# modul_aid.net
KiCad netlist of a schematic drawn in EAGLE
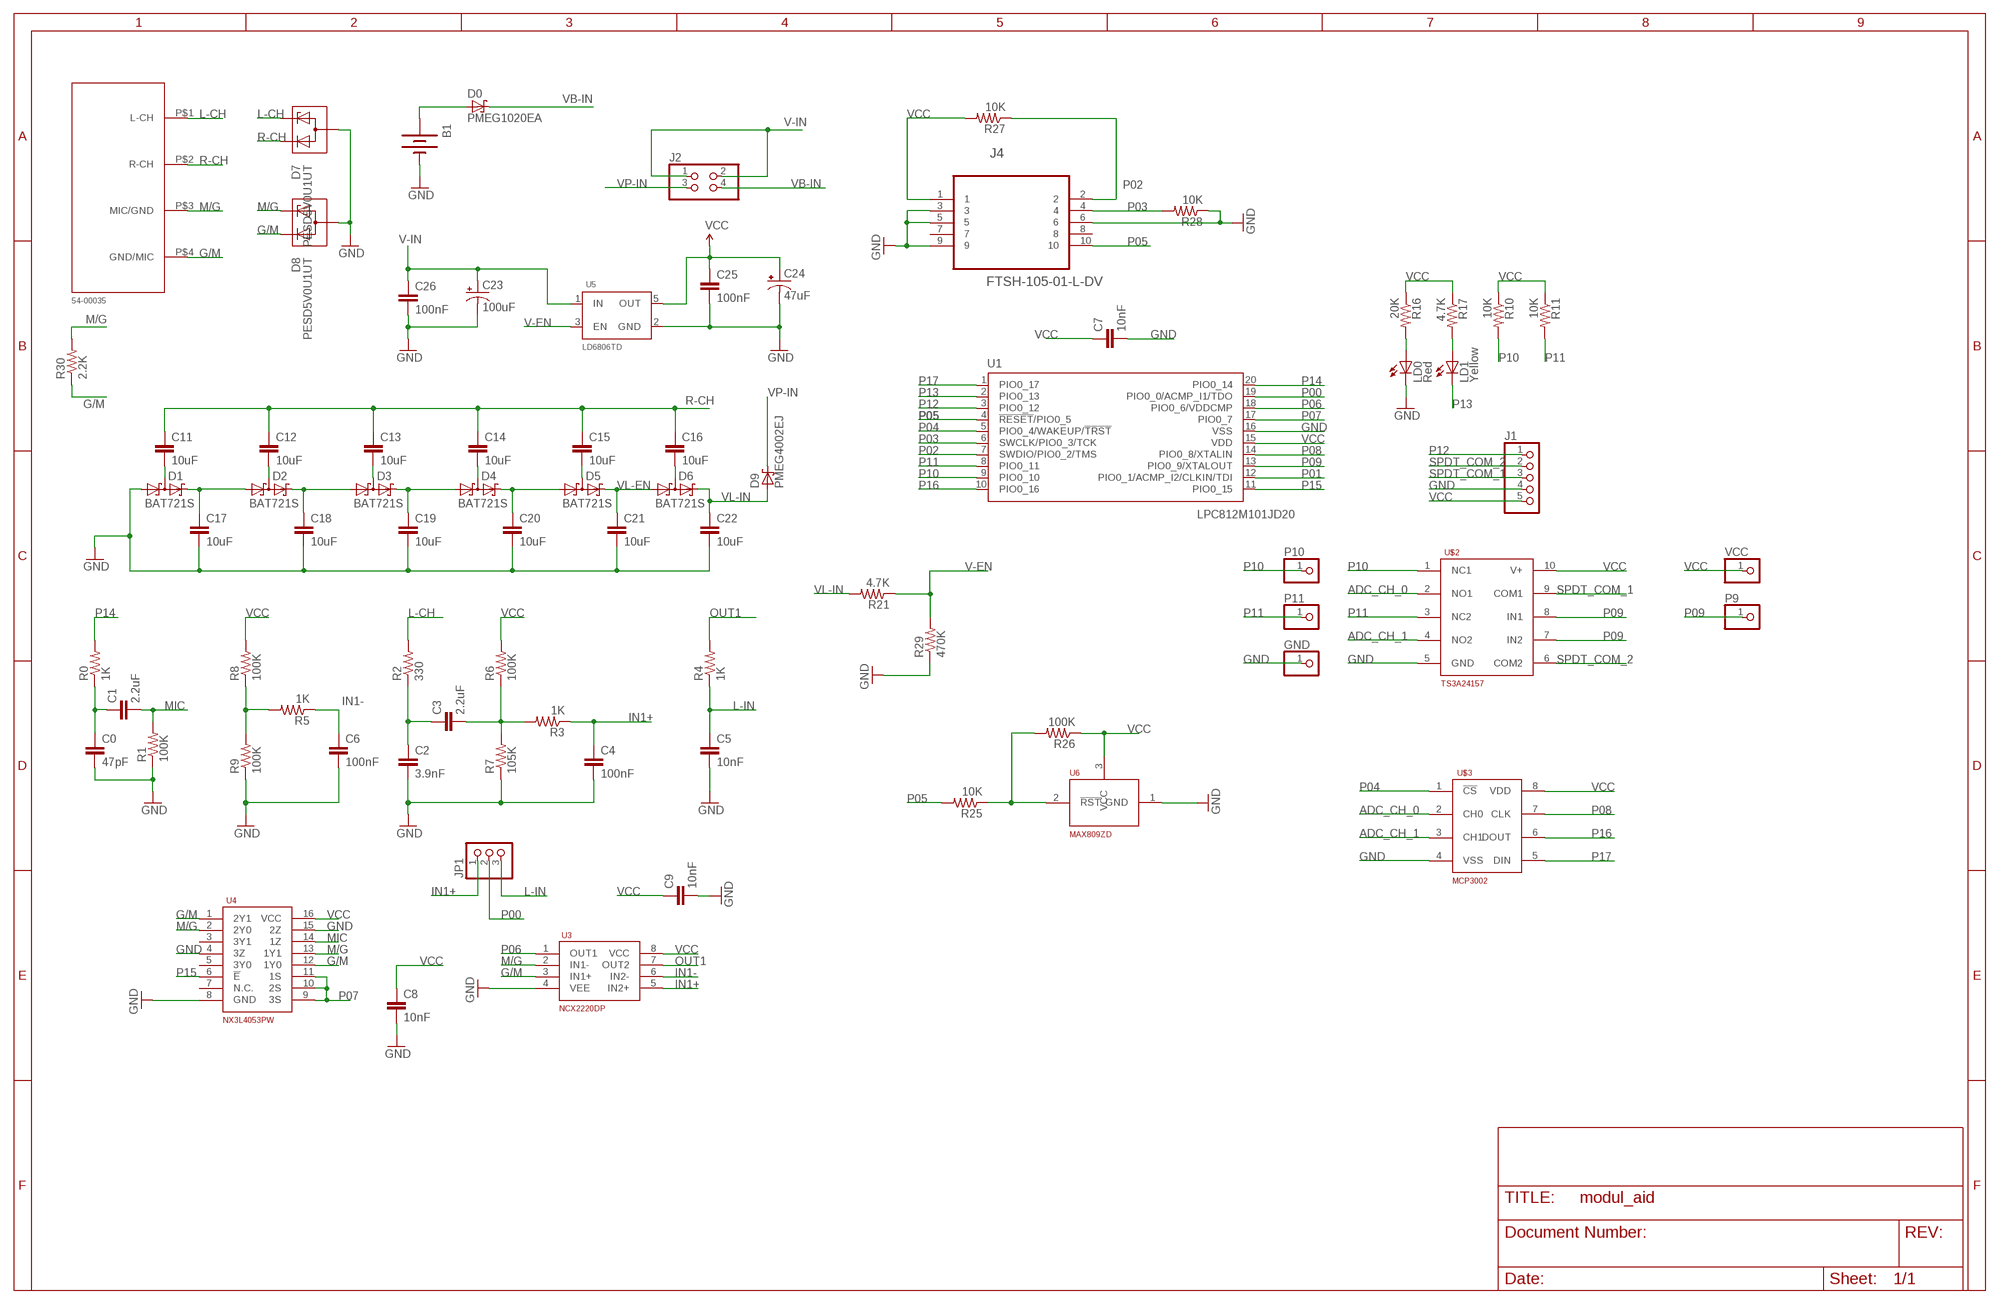
[diagram p0: schematic, sheet 1]

(export (version "E")
  (design (tool "Eeschema 10.0.6"))
  (components
    (comp (ref "B1")
      (value "BATTERY20PTH")
      (footprint "eagle-import:BATTCOM_20MM_PTH")
      (libsource (lib "eagle-import") (part "BATTERY20PTH"))
    )
    (comp (ref "C0")
      (value "47pF")
      (footprint "eagle-import:0805-CAP")
      (libsource (lib "eagle-import") (part "10UF10V10%(0805)"))
    )
    (comp (ref "C1")
      (value "2.2uF")
      (footprint "eagle-import:0805-CAP")
      (libsource (lib "eagle-import") (part "10UF10V10%(0805)"))
    )
    (comp (ref "C2")
      (value "3.9nF")
      (footprint "eagle-import:0805-CAP")
      (libsource (lib "eagle-import") (part "10UF10V10%(0805)"))
    )
    (comp (ref "C3")
      (value "2.2uF")
      (footprint "eagle-import:0805-CAP")
      (libsource (lib "eagle-import") (part "10UF10V10%(0805)"))
    )
    (comp (ref "C4")
      (value "100nF")
      (footprint "eagle-import:0805-CAP")
      (libsource (lib "eagle-import") (part "10UF10V10%(0805)"))
    )
    (comp (ref "C5")
      (value "10nF")
      (footprint "eagle-import:0805-CAP")
      (libsource (lib "eagle-import") (part "10UF10V10%(0805)"))
    )
    (comp (ref "C6")
      (value "100nF")
      (footprint "eagle-import:0805-CAP")
      (libsource (lib "eagle-import") (part "10UF10V10%(0805)"))
    )
    (comp (ref "C7")
      (value "10nF")
      (footprint "eagle-import:0805")
      (libsource (lib "eagle-import") (part "CAP0805"))
    )
    (comp (ref "C8")
      (value "10nF")
      (footprint "eagle-import:0805-CAP")
      (libsource (lib "eagle-import") (part "10UF10V10%(0805)"))
    )
    (comp (ref "C9")
      (value "10nF")
      (footprint "eagle-import:0805-CAP")
      (libsource (lib "eagle-import") (part "10UF10V10%(0805)"))
    )
    (comp (ref "C11")
      (value "10uF")
      (footprint "eagle-import:0805-CAP")
      (libsource (lib "eagle-import") (part "10UF10V10%(0805)"))
    )
    (comp (ref "C12")
      (value "10uF")
      (footprint "eagle-import:0805-CAP")
      (libsource (lib "eagle-import") (part "10UF10V10%(0805)"))
    )
    (comp (ref "C13")
      (value "10uF")
      (footprint "eagle-import:0805-CAP")
      (libsource (lib "eagle-import") (part "10UF10V10%(0805)"))
    )
    (comp (ref "C14")
      (value "10uF")
      (footprint "eagle-import:0805-CAP")
      (libsource (lib "eagle-import") (part "10UF10V10%(0805)"))
    )
    (comp (ref "C15")
      (value "10uF")
      (footprint "eagle-import:0805-CAP")
      (libsource (lib "eagle-import") (part "10UF10V10%(0805)"))
    )
    (comp (ref "C16")
      (value "10uF")
      (footprint "eagle-import:0805-CAP")
      (libsource (lib "eagle-import") (part "10UF10V10%(0805)"))
    )
    (comp (ref "C17")
      (value "10uF")
      (footprint "eagle-import:0805-CAP")
      (libsource (lib "eagle-import") (part "10UF10V10%(0805)"))
    )
    (comp (ref "C18")
      (value "10uF")
      (footprint "eagle-import:0805-CAP")
      (libsource (lib "eagle-import") (part "10UF10V10%(0805)"))
    )
    (comp (ref "C19")
      (value "10uF")
      (footprint "eagle-import:0805-CAP")
      (libsource (lib "eagle-import") (part "10UF10V10%(0805)"))
    )
    (comp (ref "C20")
      (value "10uF")
      (footprint "eagle-import:0805-CAP")
      (libsource (lib "eagle-import") (part "10UF10V10%(0805)"))
    )
    (comp (ref "C21")
      (value "10uF")
      (footprint "eagle-import:0805-CAP")
      (libsource (lib "eagle-import") (part "10UF10V10%(0805)"))
    )
    (comp (ref "C22")
      (value "10uF")
      (footprint "eagle-import:0805-CAP")
      (libsource (lib "eagle-import") (part "10UF10V10%(0805)"))
    )
    (comp (ref "C23")
      (value "100uF")
      (footprint "eagle-import:EIA3216-KIT")
      (libsource (lib "eagle-import") (part "CAP_POL1206-KIT"))
    )
    (comp (ref "C24")
      (value "47uF")
      (footprint "eagle-import:EIA3216-KIT")
      (libsource (lib "eagle-import") (part "CAP_POL1206-KIT"))
    )
    (comp (ref "C25")
      (value "100nF")
      (footprint "eagle-import:0805")
      (libsource (lib "eagle-import") (part "CAP0805"))
    )
    (comp (ref "C26")
      (value "100nF")
      (footprint "eagle-import:0805")
      (libsource (lib "eagle-import") (part "CAP0805"))
    )
    (comp (ref "D0")
      (value "PMEG1020EA")
      (footprint "eagle-import:SOD323(F)")
      (libsource (lib "eagle-import") (part "PMEG1020EA"))
    )
    (comp (ref "D1")
      (value "BAT721S")
      (footprint "eagle-import:SOT23")
      (libsource (lib "eagle-import") (part "BAT721S"))
    )
    (comp (ref "D2")
      (value "BAT721S")
      (footprint "eagle-import:SOT23")
      (libsource (lib "eagle-import") (part "BAT721S"))
    )
    (comp (ref "D3")
      (value "BAT721S")
      (footprint "eagle-import:SOT23")
      (libsource (lib "eagle-import") (part "BAT721S"))
    )
    (comp (ref "D4")
      (value "BAT721S")
      (footprint "eagle-import:SOT23")
      (libsource (lib "eagle-import") (part "BAT721S"))
    )
    (comp (ref "D5")
      (value "BAT721S")
      (footprint "eagle-import:SOT23")
      (libsource (lib "eagle-import") (part "BAT721S"))
    )
    (comp (ref "D6")
      (value "BAT721S")
      (footprint "eagle-import:SOT23")
      (libsource (lib "eagle-import") (part "BAT721S"))
    )
    (comp (ref "D7")
      (value "PESD5V0U1UT")
      (footprint "eagle-import:SOT23")
      (libsource (lib "eagle-import") (part "PESD5V0U1UT"))
    )
    (comp (ref "D8")
      (value "PESD5V0U1UT")
      (footprint "eagle-import:SOT23")
      (libsource (lib "eagle-import") (part "PESD5V0U1UT"))
    )
    (comp (ref "D9")
      (value "PMEG4002EJ")
      (footprint "eagle-import:SOD323(F)")
      (libsource (lib "eagle-import") (part "PMEG4002EJ"))
    )
    (comp (ref "GND")
      (value "PINHD-1X1")
      (footprint "eagle-import:1X01")
      (libsource (lib "eagle-import") (part "PINHD-1X1"))
    )
    (comp (ref "J1")
      (value "PINHD-1X5")
      (footprint "eagle-import:1X05")
      (libsource (lib "eagle-import") (part "PINHD-1X5"))
    )
    (comp (ref "J2")
      (value "PINHD-2X2")
      (footprint "eagle-import:2X02")
      (libsource (lib "eagle-import") (part "PINHD-2X2"))
    )
    (comp (ref "J4")
      (value "FTSH-105-01-L-DV")
      (footprint "eagle-import:SAMTEC_FTSH-105-01-L-DV")
      (libsource (lib "eagle-import") (part "FTSH-105-01-L-DV"))
    )
    (comp (ref "JP1")
      (value "PINHD-1X3")
      (footprint "eagle-import:1X03")
      (libsource (lib "eagle-import") (part "PINHD-1X3"))
    )
    (comp (ref "LD0")
      (value "Red")
      (footprint "eagle-import:SML0805")
      (libsource (lib "eagle-import") (part "LEDSML0805"))
    )
    (comp (ref "LD1")
      (value "Yellow")
      (footprint "eagle-import:SML0805")
      (libsource (lib "eagle-import") (part "LEDSML0805"))
    )
    (comp (ref "P9")
      (value "PINHD-1X1")
      (footprint "eagle-import:1X01")
      (libsource (lib "eagle-import") (part "PINHD-1X1"))
    )
    (comp (ref "P10")
      (value "PINHD-1X1")
      (footprint "eagle-import:1X01")
      (libsource (lib "eagle-import") (part "PINHD-1X1"))
    )
    (comp (ref "P11")
      (value "PINHD-1X1")
      (footprint "eagle-import:1X01")
      (libsource (lib "eagle-import") (part "PINHD-1X1"))
    )
    (comp (ref "R0")
      (value "1K")
      (footprint "eagle-import:0805")
      (libsource (lib "eagle-import") (part "RESISTOR0805-RES"))
    )
    (comp (ref "R1")
      (value "100K")
      (footprint "eagle-import:0805")
      (libsource (lib "eagle-import") (part "RESISTOR0805-RES"))
    )
    (comp (ref "R2")
      (value "330")
      (footprint "eagle-import:0805")
      (libsource (lib "eagle-import") (part "RESISTOR0805-RES"))
    )
    (comp (ref "R3")
      (value "1K")
      (footprint "eagle-import:0805")
      (libsource (lib "eagle-import") (part "RESISTOR0805-RES"))
    )
    (comp (ref "R4")
      (value "1K")
      (footprint "eagle-import:0805")
      (libsource (lib "eagle-import") (part "RESISTOR0805-RES"))
    )
    (comp (ref "R5")
      (value "1K")
      (footprint "eagle-import:0805")
      (libsource (lib "eagle-import") (part "RESISTOR0805-RES"))
    )
    (comp (ref "R6")
      (value "100K")
      (footprint "eagle-import:0805")
      (libsource (lib "eagle-import") (part "RESISTOR0805-RES"))
    )
    (comp (ref "R7")
      (value "105K")
      (footprint "eagle-import:0805")
      (libsource (lib "eagle-import") (part "RESISTOR0805-RES"))
    )
    (comp (ref "R8")
      (value "100K")
      (footprint "eagle-import:0805")
      (libsource (lib "eagle-import") (part "RESISTOR0805-RES"))
    )
    (comp (ref "R9")
      (value "100K")
      (footprint "eagle-import:0805")
      (libsource (lib "eagle-import") (part "RESISTOR0805-RES"))
    )
    (comp (ref "R10")
      (value "10K")
      (footprint "eagle-import:0805")
      (libsource (lib "eagle-import") (part "RESISTOR0805-RES"))
    )
    (comp (ref "R11")
      (value "10K")
      (footprint "eagle-import:0805")
      (libsource (lib "eagle-import") (part "RESISTOR0805-RES"))
    )
    (comp (ref "R16")
      (value "20K")
      (footprint "eagle-import:0805")
      (libsource (lib "eagle-import") (part "RESISTOR0805-RES"))
    )
    (comp (ref "R17")
      (value "4.7K")
      (footprint "eagle-import:0805")
      (libsource (lib "eagle-import") (part "RESISTOR0805-RES"))
    )
    (comp (ref "R21")
      (value "4.7K")
      (footprint "eagle-import:0805")
      (libsource (lib "eagle-import") (part "RESISTOR0805-RES"))
    )
    (comp (ref "R25")
      (value "10K")
      (footprint "eagle-import:0805")
      (libsource (lib "eagle-import") (part "RESISTOR0805-RES"))
    )
    (comp (ref "R26")
      (value "100K")
      (footprint "eagle-import:0805")
      (libsource (lib "eagle-import") (part "RESISTOR0805-RES"))
    )
    (comp (ref "R27")
      (value "10K")
      (footprint "eagle-import:0805")
      (libsource (lib "eagle-import") (part "RESISTOR0805-RES"))
    )
    (comp (ref "R28")
      (value "10K")
      (footprint "eagle-import:0805")
      (libsource (lib "eagle-import") (part "RESISTOR0805-RES"))
    )
    (comp (ref "R29")
      (value "470K")
      (footprint "eagle-import:0805")
      (libsource (lib "eagle-import") (part "RESISTOR0805-RES"))
    )
    (comp (ref "R30")
      (value "2.2K")
      (footprint "eagle-import:0805")
      (libsource (lib "eagle-import") (part "RESISTOR0805-RES"))
    )
    (comp (ref "U$2")
      (value "TS3A24157")
      (footprint "eagle-import:VSSOP-10")
      (libsource (lib "eagle-import") (part "TS3A24157"))
    )
    (comp (ref "U$3")
      (value "MCP3002")
      (footprint "eagle-import:SOIC8")
      (libsource (lib "eagle-import") (part "MCP3002"))
    )
    (comp (ref "U$4")
      (value "TENSILITY54-00035")
      (footprint "eagle-import:EE464SAUDIOJACK")
      (libsource (lib "eagle-import") (part "TENSILITY54-00035"))
    )
    (comp (ref "U1")
      (value "LPC812M101JD20")
      (footprint "eagle-import:SOT163-1")
      (libsource (lib "eagle-import") (part "LPC812M101JD20"))
    )
    (comp (ref "U3")
      (value "NCX2220DP")
      (footprint "eagle-import:SOT505-2")
      (libsource (lib "eagle-import") (part "NCX2220DP"))
    )
    (comp (ref "U4")
      (value "NX3L4053PW")
      (footprint "eagle-import:S0T403-1")
      (libsource (lib "eagle-import") (part "NX3L4053PW"))
    )
    (comp (ref "U5")
      (value "LD6806TD")
      (footprint "eagle-import:SOT753")
      (libsource (lib "eagle-import") (part "LD6806TD"))
    )
    (comp (ref "U6")
      (value "MAX809ZD")
      (footprint "eagle-import:SOT23-3")
      (libsource (lib "eagle-import") (part "MAX809ZD"))
    )
    (comp (ref "VCC")
      (value "PINHD-1X1")
      (footprint "eagle-import:1X01")
      (libsource (lib "eagle-import") (part "PINHD-1X1"))
    )
  )
  (nets
    (net (code "1") (name "/ADC_CH_0") (class "Default")
      (node (ref "U$2") (pin "2") (pinfunction "NO1_2") (pintype "bidirectional"))
      (node (ref "U$3") (pin "2") (pinfunction "CH0_2") (pintype "bidirectional"))
    )
    (net (code "2") (name "/ADC_CH_1") (class "Default")
      (node (ref "U$2") (pin "4") (pinfunction "NO2_4") (pintype "bidirectional"))
      (node (ref "U$3") (pin "3") (pinfunction "CH1_3") (pintype "bidirectional"))
    )
    (net (code "3") (name "/G{slash}M") (class "Default")
      (node (ref "D8") (pin "2") (pinfunction "KD_2") (pintype "passive"))
      (node (ref "R30") (pin "1") (pinfunction "1_1") (pintype "passive"))
      (node (ref "U$4") (pin "P$4") (pinfunction "GND/MIC_P$4") (pintype "bidirectional"))
      (node (ref "U3") (pin "3") (pinfunction "IN1+_3") (pintype "bidirectional"))
      (node (ref "U4") (pin "1") (pinfunction "2Y1_1") (pintype "bidirectional"))
      (node (ref "U4") (pin "12") (pinfunction "1Y0_12") (pintype "bidirectional"))
    )
    (net (code "4") (name "/IN1+") (class "Default")
      (node (ref "C4") (pin "1") (pinfunction "1_1") (pintype "passive"))
      (node (ref "JP1") (pin "1") (pinfunction "1_1") (pintype "passive"))
      (node (ref "R3") (pin "1") (pinfunction "1_1") (pintype "passive"))
      (node (ref "U3") (pin "5") (pinfunction "IN2+_5") (pintype "bidirectional"))
    )
    (net (code "5") (name "/IN1-") (class "Default")
      (node (ref "C6") (pin "1") (pinfunction "1_1") (pintype "passive"))
      (node (ref "R5") (pin "1") (pinfunction "1_1") (pintype "passive"))
      (node (ref "U3") (pin "6") (pinfunction "IN2-_6") (pintype "bidirectional"))
    )
    (net (code "6") (name "/L-CH") (class "Default")
      (node (ref "D7") (pin "1") (pinfunction "KESD_1") (pintype "passive"))
      (node (ref "R2") (pin "2") (pinfunction "2_2") (pintype "passive"))
      (node (ref "U$4") (pin "P$1") (pinfunction "L-CH_P$1") (pintype "bidirectional"))
    )
    (net (code "7") (name "/L-IN") (class "Default")
      (node (ref "C5") (pin "1") (pinfunction "1_1") (pintype "passive"))
      (node (ref "JP1") (pin "3") (pinfunction "3_3") (pintype "passive"))
      (node (ref "R4") (pin "1") (pinfunction "1_1") (pintype "passive"))
    )
    (net (code "8") (name "/MIC") (class "Default")
      (node (ref "C1") (pin "2") (pinfunction "2_2") (pintype "passive"))
      (node (ref "R1") (pin "2") (pinfunction "2_2") (pintype "passive"))
      (node (ref "U4") (pin "14") (pinfunction "1Z_14") (pintype "bidirectional"))
    )
    (net (code "9") (name "/M{slash}G") (class "Default")
      (node (ref "D8") (pin "1") (pinfunction "KESD_1") (pintype "passive"))
      (node (ref "R30") (pin "2") (pinfunction "2_2") (pintype "passive"))
      (node (ref "U$4") (pin "P$3") (pinfunction "MIC/GND_P$3") (pintype "bidirectional"))
      (node (ref "U3") (pin "2") (pinfunction "IN1-_2") (pintype "bidirectional"))
      (node (ref "U4") (pin "13") (pinfunction "1Y1_13") (pintype "bidirectional"))
      (node (ref "U4") (pin "2") (pinfunction "2Y0_2") (pintype "bidirectional"))
    )
    (net (code "10") (name "/OUT1") (class "Default")
      (node (ref "R4") (pin "2") (pinfunction "2_2") (pintype "passive"))
      (node (ref "U3") (pin "7") (pinfunction "OUT2_7") (pintype "bidirectional"))
    )
    (net (code "11") (name "/P00") (class "Default")
      (node (ref "JP1") (pin "2") (pinfunction "2_2") (pintype "passive"))
      (node (ref "U1") (pin "19") (pinfunction "PIO0_0/ACMP_I1/TDO_19") (pintype "bidirectional"))
    )
    (net (code "12") (name "/P01") (class "Default")
      (node (ref "U1") (pin "12") (pinfunction "PIO0_1/ACMP_I2/CLKIN/TDI_12") (pintype "bidirectional"))
    )
    (net (code "13") (name "/P02") (class "Default")
      (node (ref "J4") (pin "2") (pinfunction "2_2") (pintype "passive"))
      (node (ref "R27") (pin "1") (pinfunction "1_1") (pintype "passive"))
      (node (ref "U1") (pin "7") (pinfunction "SWDIO/PIO0_2/TMS_7") (pintype "bidirectional"))
    )
    (net (code "14") (name "/P03") (class "Default")
      (node (ref "J4") (pin "4") (pinfunction "4_4") (pintype "passive"))
      (node (ref "R28") (pin "2") (pinfunction "2_2") (pintype "passive"))
      (node (ref "U1") (pin "6") (pinfunction "SWCLK/PIO0_3/TCK_6") (pintype "bidirectional"))
    )
    (net (code "15") (name "/P04") (class "Default")
      (node (ref "U$3") (pin "1") (pinfunction "~{CS}_1") (pintype "bidirectional"))
      (node (ref "U1") (pin "5") (pinfunction "PIO0_4/WAKEUP/~{TRST}_5") (pintype "bidirectional"))
    )
    (net (code "16") (name "/P05") (class "Default")
      (node (ref "J4") (pin "10") (pinfunction "10_10") (pintype "passive"))
      (node (ref "R25") (pin "2") (pinfunction "2_2") (pintype "passive"))
      (node (ref "U1") (pin "4") (pinfunction "~{RESET}/PIO0_5_4") (pintype "bidirectional"))
    )
    (net (code "17") (name "/P06") (class "Default")
      (node (ref "U1") (pin "18") (pinfunction "PIO0_6/VDDCMP_18") (pintype "bidirectional"))
      (node (ref "U3") (pin "1") (pinfunction "OUT1_1") (pintype "bidirectional"))
    )
    (net (code "18") (name "/P07") (class "Default")
      (node (ref "U1") (pin "17") (pinfunction "PIO0_7_17") (pintype "bidirectional"))
      (node (ref "U4") (pin "10") (pinfunction "2S_10") (pintype "bidirectional"))
      (node (ref "U4") (pin "11") (pinfunction "1S_11") (pintype "bidirectional"))
      (node (ref "U4") (pin "9") (pinfunction "3S_9") (pintype "bidirectional"))
    )
    (net (code "19") (name "/P08") (class "Default")
      (node (ref "U$3") (pin "7") (pinfunction "CLK_7") (pintype "bidirectional"))
      (node (ref "U1") (pin "14") (pinfunction "PIO0_8/XTALIN_14") (pintype "bidirectional"))
    )
    (net (code "20") (name "/P09") (class "Default")
      (node (ref "P9") (pin "1") (pinfunction "1_1") (pintype "passive"))
      (node (ref "U$2") (pin "7") (pinfunction "IN2_7") (pintype "bidirectional"))
      (node (ref "U$2") (pin "8") (pinfunction "IN1_8") (pintype "bidirectional"))
      (node (ref "U1") (pin "13") (pinfunction "PIO0_9/XTALOUT_13") (pintype "bidirectional"))
    )
    (net (code "21") (name "/P10") (class "Default")
      (node (ref "P10") (pin "1") (pinfunction "1_1") (pintype "passive"))
      (node (ref "R10") (pin "2") (pinfunction "2_2") (pintype "passive"))
      (node (ref "U$2") (pin "1") (pinfunction "NC1_1") (pintype "bidirectional"))
      (node (ref "U1") (pin "9") (pinfunction "PIO0_10_9") (pintype "bidirectional"))
    )
    (net (code "22") (name "/P11") (class "Default")
      (node (ref "P11") (pin "1") (pinfunction "1_1") (pintype "passive"))
      (node (ref "R11") (pin "2") (pinfunction "2_2") (pintype "passive"))
      (node (ref "U$2") (pin "3") (pinfunction "NC2_3") (pintype "bidirectional"))
      (node (ref "U1") (pin "8") (pinfunction "PIO0_11_8") (pintype "bidirectional"))
    )
    (net (code "23") (name "/P12") (class "Default")
      (node (ref "J1") (pin "1") (pinfunction "1_1") (pintype "passive"))
      (node (ref "U1") (pin "3") (pinfunction "PIO0_12_3") (pintype "bidirectional"))
    )
    (net (code "24") (name "/P13") (class "Default")
      (node (ref "LD1") (pin "C") (pinfunction "C_C") (pintype "passive"))
      (node (ref "U1") (pin "2") (pinfunction "PIO0_13_2") (pintype "bidirectional"))
    )
    (net (code "25") (name "/P14") (class "Default")
      (node (ref "R0") (pin "2") (pinfunction "2_2") (pintype "passive"))
      (node (ref "U1") (pin "20") (pinfunction "PIO0_14_20") (pintype "bidirectional"))
    )
    (net (code "26") (name "/P15") (class "Default")
      (node (ref "U1") (pin "11") (pinfunction "PIO0_15_11") (pintype "bidirectional"))
      (node (ref "U4") (pin "6") (pinfunction "~{E}_6") (pintype "bidirectional"))
    )
    (net (code "27") (name "/P16") (class "Default")
      (node (ref "U$3") (pin "6") (pinfunction "DOUT_6") (pintype "bidirectional"))
      (node (ref "U1") (pin "10") (pinfunction "PIO0_16_10") (pintype "bidirectional"))
    )
    (net (code "28") (name "/P17") (class "Default")
      (node (ref "U$3") (pin "5") (pinfunction "DIN_5") (pintype "bidirectional"))
      (node (ref "U1") (pin "1") (pinfunction "PIO0_17_1") (pintype "bidirectional"))
    )
    (net (code "29") (name "/R-CH") (class "Default")
      (node (ref "C11") (pin "1") (pinfunction "1_1") (pintype "passive"))
      (node (ref "C12") (pin "1") (pinfunction "1_1") (pintype "passive"))
      (node (ref "C13") (pin "1") (pinfunction "1_1") (pintype "passive"))
      (node (ref "C14") (pin "1") (pinfunction "1_1") (pintype "passive"))
      (node (ref "C15") (pin "1") (pinfunction "1_1") (pintype "passive"))
      (node (ref "C16") (pin "1") (pinfunction "1_1") (pintype "passive"))
      (node (ref "D7") (pin "2") (pinfunction "KD_2") (pintype "passive"))
      (node (ref "U$4") (pin "P$2") (pinfunction "R-CH_P$2") (pintype "bidirectional"))
    )
    (net (code "30") (name "/SPDT_COM_1") (class "Default")
      (node (ref "J1") (pin "3") (pinfunction "3_3") (pintype "passive"))
      (node (ref "U$2") (pin "9") (pinfunction "COM1_9") (pintype "bidirectional"))
    )
    (net (code "31") (name "/SPDT_COM_2") (class "Default")
      (node (ref "J1") (pin "2") (pinfunction "2_2") (pintype "passive"))
      (node (ref "U$2") (pin "6") (pinfunction "COM2_6") (pintype "bidirectional"))
    )
    (net (code "32") (name "/V-EN") (class "Default")
      (node (ref "R21") (pin "1") (pinfunction "1_1") (pintype "passive"))
      (node (ref "R29") (pin "2") (pinfunction "2_2") (pintype "passive"))
      (node (ref "U5") (pin "3") (pinfunction "EN_3") (pintype "input"))
    )
    (net (code "33") (name "/V-IN") (class "Default")
      (node (ref "C23") (pin "A") (pinfunction "+_A") (pintype "passive"))
      (node (ref "C26") (pin "1") (pinfunction "1_1") (pintype "passive"))
      (node (ref "J2") (pin "1") (pinfunction "1_1") (pintype "passive"))
      (node (ref "J2") (pin "2") (pinfunction "2_2") (pintype "passive"))
      (node (ref "U5") (pin "1") (pinfunction "IN_1") (pintype "passive"))
    )
    (net (code "34") (name "/VB-IN") (class "Default")
      (node (ref "D0") (pin "1") (pinfunction "K_1") (pintype "passive"))
      (node (ref "J2") (pin "4") (pinfunction "4_4") (pintype "passive"))
    )
    (net (code "35") (name "/VL-EN") (class "Default")
      (node (ref "C21") (pin "1") (pinfunction "1_1") (pintype "passive"))
      (node (ref "D5") (pin "2") (pinfunction "K2_2") (pintype "passive"))
      (node (ref "D6") (pin "1") (pinfunction "A1_1") (pintype "passive"))
    )
    (net (code "36") (name "/VL-IN") (class "Default")
      (node (ref "C22") (pin "1") (pinfunction "1_1") (pintype "passive"))
      (node (ref "D6") (pin "2") (pinfunction "K2_2") (pintype "passive"))
      (node (ref "D9") (pin "2") (pinfunction "A_2") (pintype "passive"))
      (node (ref "R21") (pin "2") (pinfunction "2_2") (pintype "passive"))
    )
    (net (code "37") (name "/VP-IN") (class "Default")
      (node (ref "D9") (pin "1") (pinfunction "K_1") (pintype "passive"))
      (node (ref "J2") (pin "3") (pinfunction "3_3") (pintype "passive"))
    )
    (net (code "38") (name "GND") (class "Default")
      (node (ref "B1") (pin "2") (pinfunction "-_2") (pintype "power_in"))
      (node (ref "C0") (pin "2") (pinfunction "2_2") (pintype "passive"))
      (node (ref "C17") (pin "2") (pinfunction "2_2") (pintype "passive"))
      (node (ref "C18") (pin "2") (pinfunction "2_2") (pintype "passive"))
      (node (ref "C19") (pin "2") (pinfunction "2_2") (pintype "passive"))
      (node (ref "C2") (pin "2") (pinfunction "2_2") (pintype "passive"))
      (node (ref "C20") (pin "2") (pinfunction "2_2") (pintype "passive"))
      (node (ref "C21") (pin "2") (pinfunction "2_2") (pintype "passive"))
      (node (ref "C22") (pin "2") (pinfunction "2_2") (pintype "passive"))
      (node (ref "C23") (pin "C") (pinfunction "-_C") (pintype "passive"))
      (node (ref "C24") (pin "C") (pinfunction "-_C") (pintype "passive"))
      (node (ref "C25") (pin "2") (pinfunction "2_2") (pintype "passive"))
      (node (ref "C26") (pin "2") (pinfunction "2_2") (pintype "passive"))
      (node (ref "C4") (pin "2") (pinfunction "2_2") (pintype "passive"))
      (node (ref "C5") (pin "2") (pinfunction "2_2") (pintype "passive"))
      (node (ref "C6") (pin "2") (pinfunction "2_2") (pintype "passive"))
      (node (ref "C7") (pin "2") (pinfunction "2_2") (pintype "passive"))
      (node (ref "C8") (pin "2") (pinfunction "2_2") (pintype "passive"))
      (node (ref "C9") (pin "2") (pinfunction "2_2") (pintype "passive"))
      (node (ref "D1") (pin "1") (pinfunction "A1_1") (pintype "passive"))
      (node (ref "D7") (pin "3") (pinfunction "CA_3") (pintype "passive"))
      (node (ref "D8") (pin "3") (pinfunction "CA_3") (pintype "passive"))
      (node (ref "GND") (pin "1") (pinfunction "1_1") (pintype "passive"))
      (node (ref "J1") (pin "4") (pinfunction "4_4") (pintype "passive"))
      (node (ref "J4") (pin "3") (pinfunction "3_3") (pintype "passive"))
      (node (ref "J4") (pin "5") (pinfunction "5_5") (pintype "passive"))
      (node (ref "J4") (pin "6") (pinfunction "6_6") (pintype "passive"))
      (node (ref "J4") (pin "9") (pinfunction "9_9") (pintype "passive"))
      (node (ref "LD0") (pin "C") (pinfunction "C_C") (pintype "passive"))
      (node (ref "R1") (pin "1") (pinfunction "1_1") (pintype "passive"))
      (node (ref "R28") (pin "1") (pinfunction "1_1") (pintype "passive"))
      (node (ref "R29") (pin "1") (pinfunction "1_1") (pintype "passive"))
      (node (ref "R7") (pin "1") (pinfunction "1_1") (pintype "passive"))
      (node (ref "R9") (pin "1") (pinfunction "1_1") (pintype "passive"))
      (node (ref "U$2") (pin "5") (pinfunction "GND_5") (pintype "bidirectional"))
      (node (ref "U$3") (pin "4") (pinfunction "VSS_4") (pintype "bidirectional"))
      (node (ref "U1") (pin "16") (pinfunction "VSS_16") (pintype "power_in"))
      (node (ref "U3") (pin "4") (pinfunction "VEE_4") (pintype "bidirectional"))
      (node (ref "U4") (pin "15") (pinfunction "2Z_15") (pintype "bidirectional"))
      (node (ref "U4") (pin "4") (pinfunction "3Z_4") (pintype "bidirectional"))
      (node (ref "U4") (pin "8") (pinfunction "GND_8") (pintype "bidirectional"))
      (node (ref "U5") (pin "2") (pinfunction "GND_2") (pintype "power_in"))
      (node (ref "U6") (pin "1") (pinfunction "GND_1") (pintype "bidirectional"))
    )
    (net (code "39") (name "Net-(B1-+)") (class "Default")
      (node (ref "B1") (pin "1") (pinfunction "+_1") (pintype "power_in"))
      (node (ref "D0") (pin "2") (pinfunction "A_2") (pintype "passive"))
    )
    (net (code "40") (name "Net-(C0-Pad1)") (class "Default")
      (node (ref "C0") (pin "1") (pinfunction "1_1") (pintype "passive"))
      (node (ref "C1") (pin "1") (pinfunction "1_1") (pintype "passive"))
      (node (ref "R0") (pin "1") (pinfunction "1_1") (pintype "passive"))
    )
    (net (code "41") (name "Net-(C2-Pad1)") (class "Default")
      (node (ref "C2") (pin "1") (pinfunction "1_1") (pintype "passive"))
      (node (ref "C3") (pin "1") (pinfunction "1_1") (pintype "passive"))
      (node (ref "R2") (pin "1") (pinfunction "1_1") (pintype "passive"))
    )
    (net (code "42") (name "Net-(C3-Pad2)") (class "Default")
      (node (ref "C3") (pin "2") (pinfunction "2_2") (pintype "passive"))
      (node (ref "R3") (pin "2") (pinfunction "2_2") (pintype "passive"))
      (node (ref "R6") (pin "1") (pinfunction "1_1") (pintype "passive"))
      (node (ref "R7") (pin "2") (pinfunction "2_2") (pintype "passive"))
    )
    (net (code "43") (name "Net-(D1-K1A2)") (class "Default")
      (node (ref "C11") (pin "2") (pinfunction "2_2") (pintype "passive"))
      (node (ref "D1") (pin "3") (pinfunction "K1A2_3") (pintype "passive"))
    )
    (net (code "44") (name "Net-(D1-K2)") (class "Default")
      (node (ref "C17") (pin "1") (pinfunction "1_1") (pintype "passive"))
      (node (ref "D1") (pin "2") (pinfunction "K2_2") (pintype "passive"))
      (node (ref "D2") (pin "1") (pinfunction "A1_1") (pintype "passive"))
    )
    (net (code "45") (name "Net-(D2-K1A2)") (class "Default")
      (node (ref "C12") (pin "2") (pinfunction "2_2") (pintype "passive"))
      (node (ref "D2") (pin "3") (pinfunction "K1A2_3") (pintype "passive"))
    )
    (net (code "46") (name "Net-(D2-K2)") (class "Default")
      (node (ref "C18") (pin "1") (pinfunction "1_1") (pintype "passive"))
      (node (ref "D2") (pin "2") (pinfunction "K2_2") (pintype "passive"))
      (node (ref "D3") (pin "1") (pinfunction "A1_1") (pintype "passive"))
    )
    (net (code "47") (name "Net-(D3-K1A2)") (class "Default")
      (node (ref "C13") (pin "2") (pinfunction "2_2") (pintype "passive"))
      (node (ref "D3") (pin "3") (pinfunction "K1A2_3") (pintype "passive"))
    )
    (net (code "48") (name "Net-(D3-K2)") (class "Default")
      (node (ref "C19") (pin "1") (pinfunction "1_1") (pintype "passive"))
      (node (ref "D3") (pin "2") (pinfunction "K2_2") (pintype "passive"))
      (node (ref "D4") (pin "1") (pinfunction "A1_1") (pintype "passive"))
    )
    (net (code "49") (name "Net-(D4-K1A2)") (class "Default")
      (node (ref "C14") (pin "2") (pinfunction "2_2") (pintype "passive"))
      (node (ref "D4") (pin "3") (pinfunction "K1A2_3") (pintype "passive"))
    )
    (net (code "50") (name "Net-(D4-K2)") (class "Default")
      (node (ref "C20") (pin "1") (pinfunction "1_1") (pintype "passive"))
      (node (ref "D4") (pin "2") (pinfunction "K2_2") (pintype "passive"))
      (node (ref "D5") (pin "1") (pinfunction "A1_1") (pintype "passive"))
    )
    (net (code "51") (name "Net-(D5-K1A2)") (class "Default")
      (node (ref "C15") (pin "2") (pinfunction "2_2") (pintype "passive"))
      (node (ref "D5") (pin "3") (pinfunction "K1A2_3") (pintype "passive"))
    )
    (net (code "52") (name "Net-(D6-K1A2)") (class "Default")
      (node (ref "C16") (pin "2") (pinfunction "2_2") (pintype "passive"))
      (node (ref "D6") (pin "3") (pinfunction "K1A2_3") (pintype "passive"))
    )
    (net (code "53") (name "Net-(LD0-PadA)") (class "Default")
      (node (ref "LD0") (pin "A") (pinfunction "A_A") (pintype "passive"))
      (node (ref "R16") (pin "2") (pinfunction "2_2") (pintype "passive"))
    )
    (net (code "54") (name "Net-(LD1-PadA)") (class "Default")
      (node (ref "LD1") (pin "A") (pinfunction "A_A") (pintype "passive"))
      (node (ref "R17") (pin "2") (pinfunction "2_2") (pintype "passive"))
    )
    (net (code "55") (name "Net-(R5-Pad2)") (class "Default")
      (node (ref "R5") (pin "2") (pinfunction "2_2") (pintype "passive"))
      (node (ref "R8") (pin "1") (pinfunction "1_1") (pintype "passive"))
      (node (ref "R9") (pin "2") (pinfunction "2_2") (pintype "passive"))
    )
    (net (code "56") (name "Net-(U6-~{RST})") (class "Default")
      (node (ref "R25") (pin "1") (pinfunction "1_1") (pintype "passive"))
      (node (ref "R26") (pin "2") (pinfunction "2_2") (pintype "passive"))
      (node (ref "U6") (pin "2") (pinfunction "~{RST}_2") (pintype "bidirectional"))
    )
    (net (code "57") (name "VCC") (class "Default")
      (node (ref "C24") (pin "A") (pinfunction "+_A") (pintype "passive"))
      (node (ref "C25") (pin "1") (pinfunction "1_1") (pintype "passive"))
      (node (ref "C7") (pin "1") (pinfunction "1_1") (pintype "passive"))
      (node (ref "C8") (pin "1") (pinfunction "1_1") (pintype "passive"))
      (node (ref "C9") (pin "1") (pinfunction "1_1") (pintype "passive"))
      (node (ref "J1") (pin "5") (pinfunction "5_5") (pintype "passive"))
      (node (ref "J4") (pin "1") (pinfunction "1_1") (pintype "passive"))
      (node (ref "R10") (pin "1") (pinfunction "1_1") (pintype "passive"))
      (node (ref "R11") (pin "1") (pinfunction "1_1") (pintype "passive"))
      (node (ref "R16") (pin "1") (pinfunction "1_1") (pintype "passive"))
      (node (ref "R17") (pin "1") (pinfunction "1_1") (pintype "passive"))
      (node (ref "R26") (pin "1") (pinfunction "1_1") (pintype "passive"))
      (node (ref "R27") (pin "2") (pinfunction "2_2") (pintype "passive"))
      (node (ref "R6") (pin "2") (pinfunction "2_2") (pintype "passive"))
      (node (ref "R8") (pin "2") (pinfunction "2_2") (pintype "passive"))
      (node (ref "U$2") (pin "10") (pinfunction "V+_10") (pintype "bidirectional"))
      (node (ref "U$3") (pin "8") (pinfunction "VDD_8") (pintype "bidirectional"))
      (node (ref "U1") (pin "15") (pinfunction "VDD_15") (pintype "power_in"))
      (node (ref "U3") (pin "8") (pinfunction "VCC_8") (pintype "bidirectional"))
      (node (ref "U4") (pin "16") (pinfunction "VCC_16") (pintype "bidirectional"))
      (node (ref "U5") (pin "5") (pinfunction "OUT_5") (pintype "passive"))
      (node (ref "U6") (pin "3") (pinfunction "VCC_3") (pintype "bidirectional"))
      (node (ref "VCC") (pin "1") (pinfunction "1_1") (pintype "passive"))
    )
    (net (code "58") (name "unconnected-(J4-Pad7)") (class "Default")
      (node (ref "J4") (pin "7") (pinfunction "7_7") (pintype "passive"))
    )
    (net (code "59") (name "unconnected-(J4-Pad8)") (class "Default")
      (node (ref "J4") (pin "8") (pinfunction "8_8") (pintype "passive"))
    )
    (net (code "60") (name "unconnected-(U4-3Y0-Pad5)") (class "Default")
      (node (ref "U4") (pin "5") (pinfunction "3Y0_5") (pintype "bidirectional"))
    )
    (net (code "61") (name "unconnected-(U4-3Y1-Pad3)") (class "Default")
      (node (ref "U4") (pin "3") (pinfunction "3Y1_3") (pintype "bidirectional"))
    )
    (net (code "62") (name "unconnected-(U4-N.C.-Pad7)") (class "Default")
      (node (ref "U4") (pin "7") (pinfunction "N.C._7") (pintype "bidirectional"))
    )
  )
)
